# 2230506226.net
KiCad netlist of a schematic drawn in EasyEDA Pro
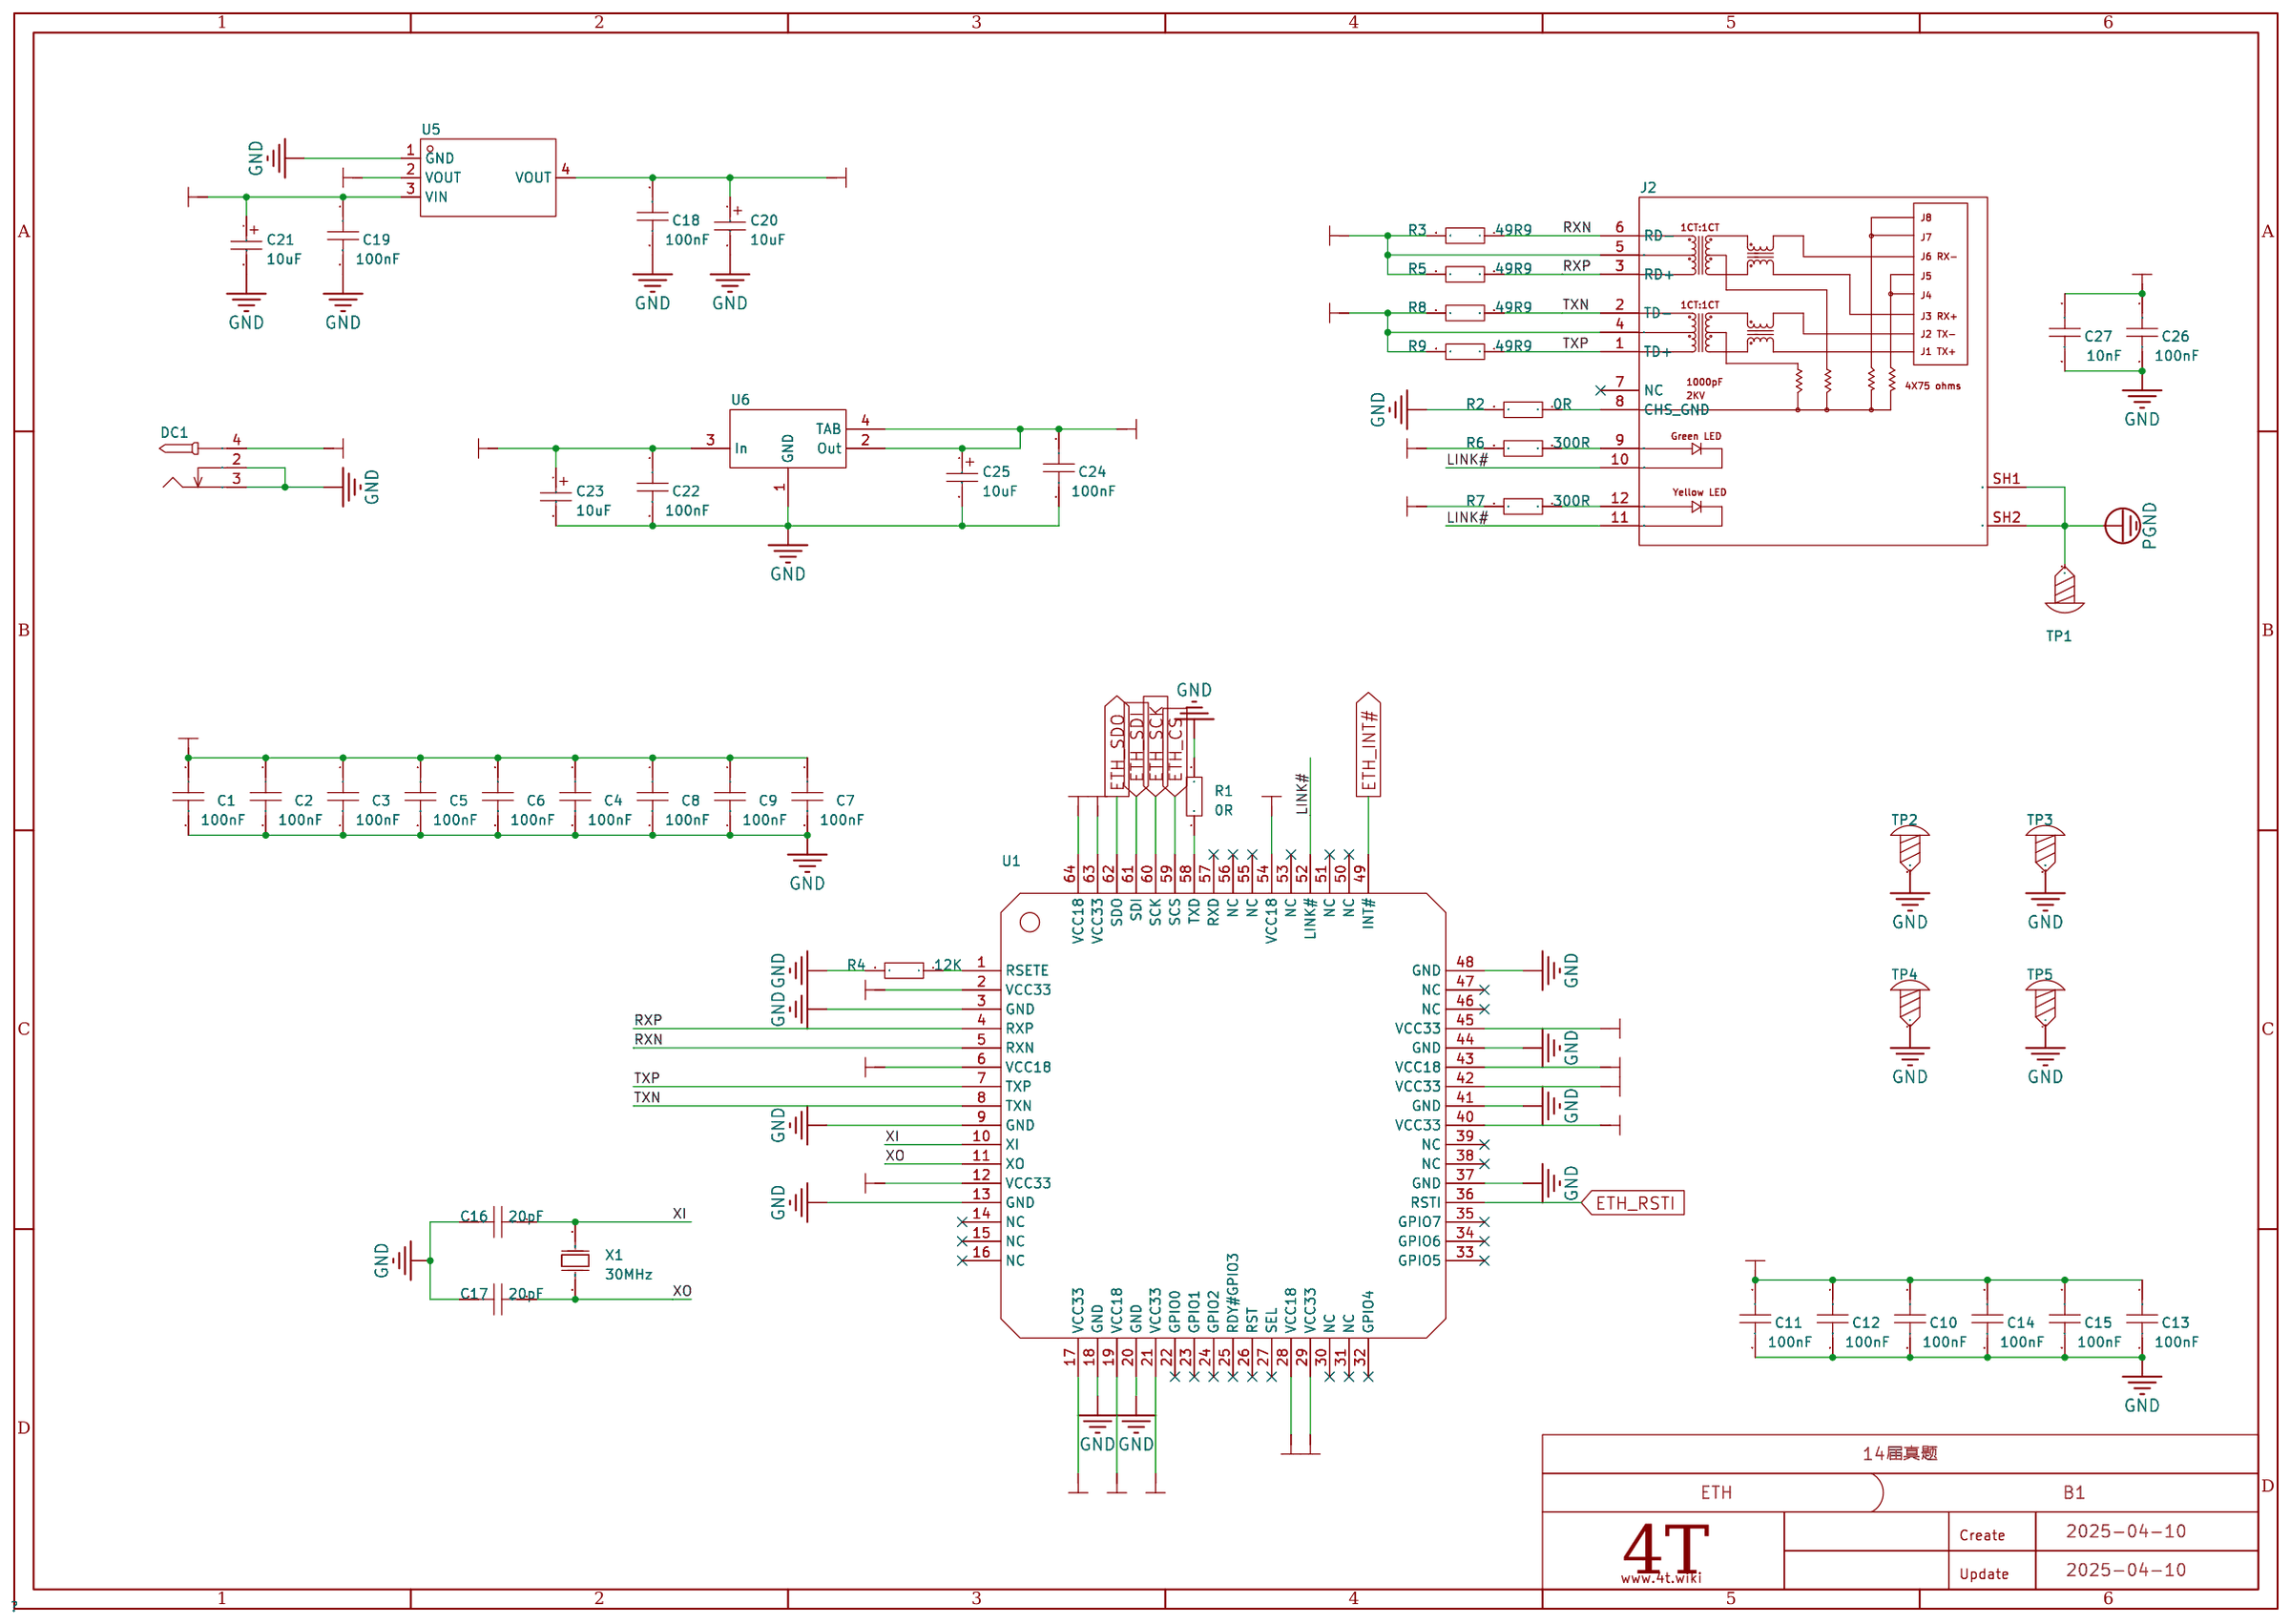
[diagram p0: ETH]
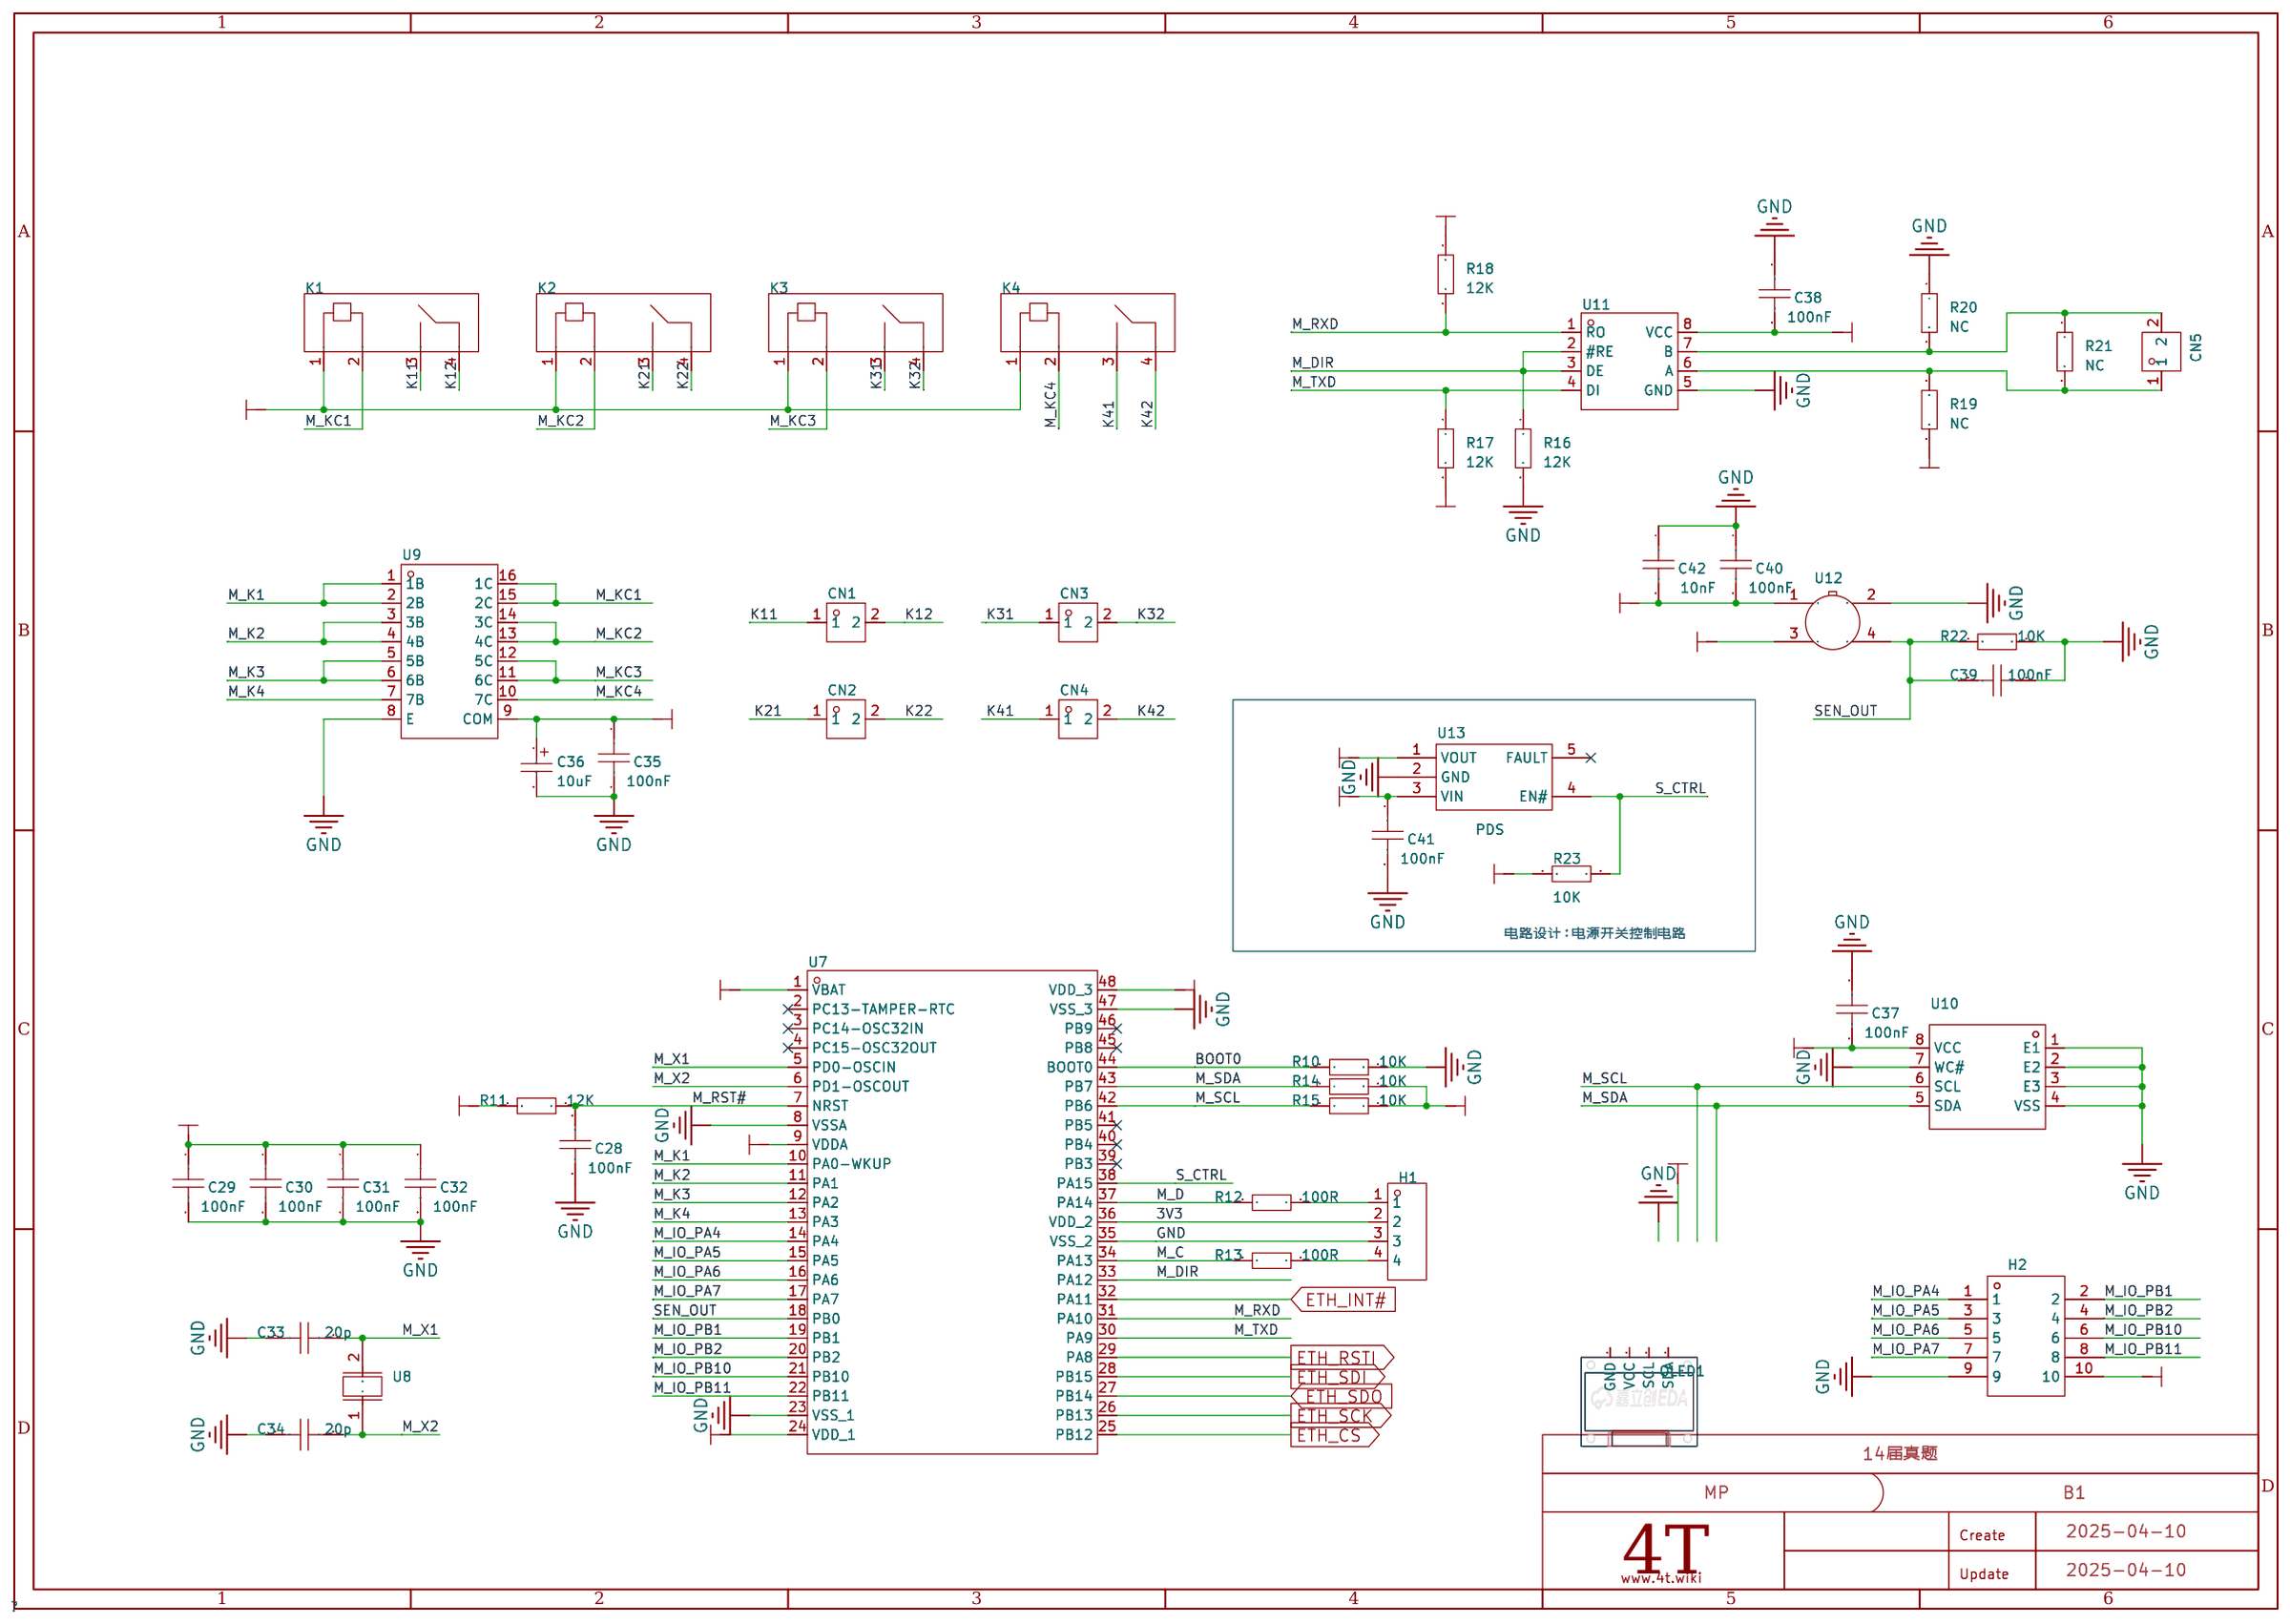
[diagram p1: MP]

(export (version "E")
  (design (tool "Eeschema 10.0.6"))
  (components
    (comp (ref "C1")
      (value "100nF")
      (footprint "easyedapro:C0805")
      (libsource (lib "easyedapro") (part "CapAcitance"))
    )
    (comp (ref "C2")
      (value "100nF")
      (footprint "easyedapro:C0805")
      (libsource (lib "easyedapro") (part "CapAcitance"))
    )
    (comp (ref "C3")
      (value "100nF")
      (footprint "easyedapro:C0805")
      (libsource (lib "easyedapro") (part "CapAcitance"))
    )
    (comp (ref "C4")
      (value "100nF")
      (footprint "easyedapro:C0805")
      (libsource (lib "easyedapro") (part "CapAcitance"))
    )
    (comp (ref "C5")
      (value "100nF")
      (footprint "easyedapro:C0805")
      (libsource (lib "easyedapro") (part "CapAcitance"))
    )
    (comp (ref "C6")
      (value "100nF")
      (footprint "easyedapro:C0805")
      (libsource (lib "easyedapro") (part "CapAcitance"))
    )
    (comp (ref "C7")
      (value "100nF")
      (footprint "easyedapro:C0805")
      (libsource (lib "easyedapro") (part "CapAcitance"))
    )
    (comp (ref "C8")
      (value "100nF")
      (footprint "easyedapro:C0805")
      (libsource (lib "easyedapro") (part "CapAcitance"))
    )
    (comp (ref "C9")
      (value "100nF")
      (footprint "easyedapro:C0805")
      (libsource (lib "easyedapro") (part "CapAcitance"))
    )
    (comp (ref "C10")
      (value "100nF")
      (footprint "easyedapro:C0805")
      (libsource (lib "easyedapro") (part "CapAcitance"))
    )
    (comp (ref "C11")
      (value "100nF")
      (footprint "easyedapro:C0805")
      (libsource (lib "easyedapro") (part "CapAcitance"))
    )
    (comp (ref "C12")
      (value "100nF")
      (footprint "easyedapro:C0805")
      (libsource (lib "easyedapro") (part "CapAcitance"))
    )
    (comp (ref "C13")
      (value "100nF")
      (footprint "easyedapro:C0805")
      (libsource (lib "easyedapro") (part "CapAcitance"))
    )
    (comp (ref "C14")
      (value "100nF")
      (footprint "easyedapro:C0805")
      (libsource (lib "easyedapro") (part "CapAcitance"))
    )
    (comp (ref "C15")
      (value "100nF")
      (footprint "easyedapro:C0805")
      (libsource (lib "easyedapro") (part "CapAcitance"))
    )
    (comp (ref "C16")
      (value "20pF")
      (footprint "easyedapro:C0805")
      (libsource (lib "easyedapro") (part "CapAcitance"))
    )
    (comp (ref "C17")
      (value "20pF")
      (footprint "easyedapro:C0805")
      (libsource (lib "easyedapro") (part "CapAcitance"))
    )
    (comp (ref "C18")
      (value "100nF")
      (footprint "easyedapro:C0805")
      (libsource (lib "easyedapro") (part "CapAcitance"))
    )
    (comp (ref "C19")
      (value "100nF")
      (footprint "easyedapro:C0805")
      (libsource (lib "easyedapro") (part "CapAcitance"))
    )
    (comp (ref "C20")
      (value "10uF")
      (footprint "easyedapro:C_Ele_SMD_3x5.4mm")
      (libsource (lib "easyedapro") (part "CAP"))
    )
    (comp (ref "C21")
      (value "10uF")
      (footprint "easyedapro:C_Ele_SMD_3x5.4mm")
      (libsource (lib "easyedapro") (part "CAP"))
    )
    (comp (ref "C22")
      (value "100nF")
      (footprint "easyedapro:C0805")
      (libsource (lib "easyedapro") (part "CapAcitance"))
    )
    (comp (ref "C23")
      (value "10uF")
      (footprint "easyedapro:C_Ele_SMD_3x5.4mm")
      (libsource (lib "easyedapro") (part "CAP"))
    )
    (comp (ref "C24")
      (value "100nF")
      (footprint "easyedapro:C0805")
      (libsource (lib "easyedapro") (part "CapAcitance"))
    )
    (comp (ref "C25")
      (value "10uF")
      (footprint "easyedapro:C_Ele_SMD_3x5.4mm")
      (libsource (lib "easyedapro") (part "CAP"))
    )
    (comp (ref "C26")
      (value "100nF")
      (footprint "easyedapro:C0805")
      (libsource (lib "easyedapro") (part "CapAcitance"))
    )
    (comp (ref "C27")
      (value "10nF")
      (footprint "easyedapro:C0805")
      (libsource (lib "easyedapro") (part "CapAcitance"))
    )
    (comp (ref "DC1")
      (value "~")
      (footprint "easyedapro:DC-2.0")
      (libsource (lib "easyedapro") (part "DC电源接口"))
    )
    (comp (ref "J2")
      (value "HY911105AE")
      (footprint "easyedapro:RJ45-TH_HR911105A")
      (description "连接器类型:RJ插座;USOC代码:RJ45;端口数量:1;等级:-;屏蔽:-;LED:-;")
      (fields (field (name "Manufacturer") "HANRUN(汉仁)"))
      (libsource (lib "easyedapro") (part "HY911105AE"))
    )
    (comp (ref "R1") (value "0R") (footprint "easyedapro:R0805") (libsource (lib "easyedapro") (part "电阻")))
    (comp (ref "R2") (value "0R") (footprint "easyedapro:R0805") (libsource (lib "easyedapro") (part "电阻")))
    (comp (ref "R3") (value "49R9") (footprint "easyedapro:R0805") (libsource (lib "easyedapro") (part "电阻")))
    (comp (ref "R4") (value "12K") (footprint "easyedapro:R0805") (libsource (lib "easyedapro") (part "电阻")))
    (comp (ref "R5") (value "49R9") (footprint "easyedapro:R0805") (libsource (lib "easyedapro") (part "电阻")))
    (comp (ref "R6") (value "300R") (footprint "easyedapro:R0805") (libsource (lib "easyedapro") (part "电阻")))
    (comp (ref "R7") (value "300R") (footprint "easyedapro:R0805") (libsource (lib "easyedapro") (part "电阻")))
    (comp (ref "R8") (value "49R9") (footprint "easyedapro:R0805") (libsource (lib "easyedapro") (part "电阻")))
    (comp (ref "R9") (value "49R9") (footprint "easyedapro:R0805") (libsource (lib "easyedapro") (part "电阻")))
    (comp (ref "TP1") (value "~") (footprint "easyedapro:M2螺丝") (libsource (lib "easyedapro") (part "螺丝孔")))
    (comp (ref "TP2") (value "~") (footprint "easyedapro:M2螺丝") (libsource (lib "easyedapro") (part "螺丝孔")))
    (comp (ref "TP3") (value "~") (footprint "easyedapro:M2螺丝") (libsource (lib "easyedapro") (part "螺丝孔")))
    (comp (ref "TP4") (value "~") (footprint "easyedapro:M2螺丝") (libsource (lib "easyedapro") (part "螺丝孔")))
    (comp (ref "TP5") (value "~") (footprint "easyedapro:M2螺丝") (libsource (lib "easyedapro") (part "螺丝孔")))
    (comp (ref "U1")
      (value "CH395Q")
      (footprint "easyedapro:LQFP-64_L10.0-W10.0-P0.50-LS12.0-BL")
      (description "应用功能:以太网控制器;通道数:-;接口类型:Parallel, SPI, UART;电源电压:1.65V~3.6V;电源电流:90mA;")
      (fields (field (name "Manufacturer") "WCH(南京沁恒)"))
      (libsource (lib "easyedapro") (part "CH395Q"))
    )
    (comp (ref "U5")
      (value "AMS1117-3.3")
      (footprint "easyedapro:SOT-223-3_L6.5-W3.4-P2.30-LS7.0-BR")
      (fields (field (name "Manufacturer") "AMS"))
      (libsource (lib "easyedapro") (part "AMS1117-3.3"))
    )
    (comp (ref "U6")
      (value "AMS1117-1.8")
      (footprint "easyedapro:SOT-223-4_L6.5-W3.5-P2.30-LS7.0-BR")
      (description "输出类型:固定;输出极性:正;输出通道数:1;最大输入电压:15V;输出电压:1.8V~1.8V;压差:1.3V@(1A);输出电流:1A;电源纹波抑制比(PSRR):75dB@(120Hz);")
      (fields (field (name "Manufacturer") "AMS"))
      (libsource (lib "easyedapro") (part "AMS1117-1.8"))
    )
    (comp (ref "X1")
      (value "30MHz")
      (footprint "easyedapro:OSC-SMD_L5.0-W3.2")
      (description "晶振类型:贴片无源晶振;频率:30MHz;频率公差:±10ppm;频率稳定度:±50ppm;负载电容:20pF;工作温度:-40°C~+85°C;")
      (fields (field (name "Manufacturer Part") "X503230MSB2GI") (field (name "Manufacturer") "YXC(扬兴晶振)"))
      (libsource (lib "easyedapro") (part "X503230MSB2GI"))
    )
    (comp (ref "C28")
      (value "100nF")
      (footprint "easyedapro:C0805")
      (libsource (lib "easyedapro") (part "CapAcitance"))
    )
    (comp (ref "C29")
      (value "100nF")
      (footprint "easyedapro:C0805")
      (libsource (lib "easyedapro") (part "CapAcitance"))
    )
    (comp (ref "C30")
      (value "100nF")
      (footprint "easyedapro:C0805")
      (libsource (lib "easyedapro") (part "CapAcitance"))
    )
    (comp (ref "C31")
      (value "100nF")
      (footprint "easyedapro:C0805")
      (libsource (lib "easyedapro") (part "CapAcitance"))
    )
    (comp (ref "C32")
      (value "100nF")
      (footprint "easyedapro:C0805")
      (libsource (lib "easyedapro") (part "CapAcitance"))
    )
    (comp (ref "C33")
      (value "20p")
      (footprint "easyedapro:C0805")
      (libsource (lib "easyedapro") (part "CapAcitance"))
    )
    (comp (ref "C34")
      (value "20p")
      (footprint "easyedapro:C0805")
      (libsource (lib "easyedapro") (part "CapAcitance"))
    )
    (comp (ref "C35")
      (value "100nF")
      (footprint "easyedapro:C0805")
      (libsource (lib "easyedapro") (part "CapAcitance"))
    )
    (comp (ref "C36")
      (value "10uF")
      (footprint "easyedapro:C_Ele_SMD_3x5.4mm")
      (libsource (lib "easyedapro") (part "CAP"))
    )
    (comp (ref "C37")
      (value "100nF")
      (footprint "easyedapro:C0805")
      (libsource (lib "easyedapro") (part "CapAcitance"))
    )
    (comp (ref "C38")
      (value "100nF")
      (footprint "easyedapro:C0805")
      (libsource (lib "easyedapro") (part "CapAcitance"))
    )
    (comp (ref "C39")
      (value "100nF")
      (footprint "easyedapro:C0805")
      (libsource (lib "easyedapro") (part "CapAcitance"))
    )
    (comp (ref "C40")
      (value "100nF")
      (footprint "easyedapro:C0805")
      (libsource (lib "easyedapro") (part "CapAcitance"))
    )
    (comp (ref "C41")
      (value "100nF")
      (footprint "easyedapro:C0805")
      (libsource (lib "easyedapro") (part "CapAcitance"))
    )
    (comp (ref "C42")
      (value "10nF")
      (footprint "easyedapro:C0805")
      (libsource (lib "easyedapro") (part "CapAcitance"))
    )
    (comp (ref "CN1")
      (value "KF128L-5.08-2P 蓝色")
      (footprint "easyedapro:TH_KF128L-5.08-2P")
      (libsource (lib "easyedapro") (part "KF128L-5.08-2P 蓝色"))
    )
    (comp (ref "CN2")
      (value "KF128L-5.08-2P 蓝色")
      (footprint "easyedapro:TH_KF128L-5.08-2P")
      (libsource (lib "easyedapro") (part "KF128L-5.08-2P 蓝色"))
    )
    (comp (ref "CN3")
      (value "KF128L-5.08-2P 蓝色")
      (footprint "easyedapro:TH_KF128L-5.08-2P")
      (libsource (lib "easyedapro") (part "KF128L-5.08-2P 蓝色"))
    )
    (comp (ref "CN4")
      (value "KF128L-5.08-2P 蓝色")
      (footprint "easyedapro:TH_KF128L-5.08-2P")
      (libsource (lib "easyedapro") (part "KF128L-5.08-2P 蓝色"))
    )
    (comp (ref "CN5")
      (value "KF128L-5.08-2P 蓝色")
      (footprint "easyedapro:TH_KF128L-5.08-2P")
      (libsource (lib "easyedapro") (part "KF128L-5.08-2P 蓝色"))
    )
    (comp (ref "H1")
      (value "~")
      (footprint "easyedapro:HDR-TH_4P-P2.54-V-F")
      (libsource (lib "easyedapro") (part "2.54-1*4P母"))
    )
    (comp (ref "H2")
      (value "~")
      (footprint "easyedapro:HDR-TH_10P-P2.54-V-M-R2-C5-S2.54")
      (libsource (lib "easyedapro") (part "HDR-M-2.54_2x5"))
    )
    (comp (ref "K1")
      (value "HF49FD/012-1H12")
      (footprint "easyedapro:RELAY-TH_HF49FD-XXX-1H12-XXX")
      (description "线圈电压:12V;线圈类型:非极化-单线圈;触点形式:一组常开:1A(单刀单掷-常开);最大切换电流:5A;触点材料:AgNi;")
      (fields (field (name "Manufacturer") "HF(宏发)"))
      (libsource (lib "easyedapro") (part "HF49FD/012-1H12"))
    )
    (comp (ref "K2")
      (value "HF49FD/012-1H12")
      (footprint "easyedapro:RELAY-TH_HF49FD-XXX-1H12-XXX")
      (description "线圈电压:12V;线圈类型:非极化-单线圈;触点形式:一组常开:1A(单刀单掷-常开);最大切换电流:5A;触点材料:AgNi;")
      (fields (field (name "Manufacturer") "HF(宏发)"))
      (libsource (lib "easyedapro") (part "HF49FD/012-1H12"))
    )
    (comp (ref "K3")
      (value "HF49FD/012-1H12")
      (footprint "easyedapro:RELAY-TH_HF49FD-XXX-1H12-XXX")
      (description "线圈电压:12V;线圈类型:非极化-单线圈;触点形式:一组常开:1A(单刀单掷-常开);最大切换电流:5A;触点材料:AgNi;")
      (fields (field (name "Manufacturer") "HF(宏发)"))
      (libsource (lib "easyedapro") (part "HF49FD/012-1H12"))
    )
    (comp (ref "K4")
      (value "HF49FD/012-1H12")
      (footprint "easyedapro:RELAY-TH_HF49FD-XXX-1H12-XXX")
      (description "线圈电压:12V;线圈类型:非极化-单线圈;触点形式:一组常开:1A(单刀单掷-常开);最大切换电流:5A;触点材料:AgNi;")
      (fields (field (name "Manufacturer") "HF(宏发)"))
      (libsource (lib "easyedapro") (part "HF49FD/012-1H12"))
    )
    (comp (ref "OLED1")
      (value "~")
      (footprint "easyedapro:0.96OLED_4P")
      (libsource (lib "easyedapro") (part "0.96OLED模块_4P"))
    )
    (comp (ref "R10") (value "10K") (footprint "easyedapro:R0805") (libsource (lib "easyedapro") (part "电阻")))
    (comp (ref "R11") (value "12K") (footprint "easyedapro:R0805") (libsource (lib "easyedapro") (part "电阻")))
    (comp (ref "R12")
      (value "100R")
      (footprint "easyedapro:R0805")
      (libsource (lib "easyedapro") (part "电阻"))
    )
    (comp (ref "R13")
      (value "100R")
      (footprint "easyedapro:R0805")
      (libsource (lib "easyedapro") (part "电阻"))
    )
    (comp (ref "R14") (value "10K") (footprint "easyedapro:R0805") (libsource (lib "easyedapro") (part "电阻")))
    (comp (ref "R15") (value "10K") (footprint "easyedapro:R0805") (libsource (lib "easyedapro") (part "电阻")))
    (comp (ref "R16") (value "12K") (footprint "easyedapro:R0805") (libsource (lib "easyedapro") (part "电阻")))
    (comp (ref "R17") (value "12K") (footprint "easyedapro:R0805") (libsource (lib "easyedapro") (part "电阻")))
    (comp (ref "R18") (value "12K") (footprint "easyedapro:R0805") (libsource (lib "easyedapro") (part "电阻")))
    (comp (ref "R19") (value "NC") (footprint "easyedapro:R0805") (libsource (lib "easyedapro") (part "电阻")))
    (comp (ref "R20") (value "NC") (footprint "easyedapro:R0805") (libsource (lib "easyedapro") (part "电阻")))
    (comp (ref "R21") (value "NC") (footprint "easyedapro:R0805") (libsource (lib "easyedapro") (part "电阻")))
    (comp (ref "R22") (value "10K") (footprint "easyedapro:R0805") (libsource (lib "easyedapro") (part "电阻")))
    (comp (ref "R23") (value "10K") (footprint "easyedapro:R0805") (libsource (lib "easyedapro") (part "电阻")))
    (comp (ref "U7")
      (value "GD32F303CBT6")
      (footprint "easyedapro:LQFP-48_L7.0-W7.0-P0.50-LS9.0-BL")
      (fields (field (name "Manufacturer") "GigaDevice(兆易创新)"))
      (libsource (lib "easyedapro") (part "GD32F303CBT6"))
    )
    (comp (ref "U8")
      (value "8M-5032-2P")
      (footprint "easyedapro:CRYSTAL-SMD_L5.0-W3.2")
      (libsource (lib "easyedapro") (part "8M-5032-2P"))
    )
    (comp (ref "U9")
      (value "ULN2003")
      (footprint "easyedapro:SOIC-16_L9.9-W3.9-P1.27-LS6.0-BL")
      (fields (field (name "Manufacturer") "IDCHIP(英锐芯)"))
      (libsource (lib "easyedapro") (part "ULN2003_C688859"))
    )
    (comp (ref "U10")
      (value "M24C02-WMN6TP")
      (footprint "easyedapro:SOIC-8_L4.9-W3.9-P1.27-LS6.0-BL")
      (description "2-Kbit(256 x 8bit)，I2C接口，工作电压：2.5V to 5.5V")
      (fields (field (name "Manufacturer") "ST(意法半导体)"))
      (libsource (lib "easyedapro") (part "M24C02-WMN6TP"))
    )
    (comp (ref "U11")
      (value "MAX3485ESA")
      (footprint "easyedapro:SOP-8_L5.0-W4.0-P1.27-LS6.0-BL")
      (fields (field (name "Manufacturer") "UMW(广东友台半导体)"))
      (libsource (lib "easyedapro") (part "MAX3485ESA"))
    )
    (comp (ref "U12")
      (value "MP-2")
      (footprint "easyedapro:SENSOR-TH_MP-5")
      (fields (field (name "Manufacturer") "Winsen(炜盛)"))
      (libsource (lib "easyedapro") (part "MP-2"))
    )
    (comp (ref "U13") (value "PDS") (libsource (lib "easyedapro") (part "PDS")))
  )
  (nets
    (net (code "1") (name "1V8") (class "Default")
      (node (ref "C10") (pin "1") (pinfunction "1_1") (pintype "input"))
      (node (ref "C11") (pin "1") (pinfunction "1_1") (pintype "input"))
      (node (ref "C12") (pin "1") (pinfunction "1_1") (pintype "input"))
      (node (ref "C13") (pin "1") (pinfunction "1_1") (pintype "input"))
      (node (ref "C14") (pin "1") (pinfunction "1_1") (pintype "input"))
      (node (ref "C15") (pin "1") (pinfunction "1_1") (pintype "input"))
      (node (ref "C24") (pin "1") (pinfunction "1_1") (pintype "input"))
      (node (ref "C25") (pin "1") (pinfunction "1_1") (pintype "input"))
      (node (ref "U1") (pin "19") (pinfunction "VCC18_19") (pintype "input"))
      (node (ref "U1") (pin "28") (pinfunction "VCC18_28") (pintype "input"))
      (node (ref "U1") (pin "43") (pinfunction "VCC18_43") (pintype "input"))
      (node (ref "U1") (pin "54") (pinfunction "VCC18_54") (pintype "input"))
      (node (ref "U1") (pin "6") (pinfunction "VCC18_6") (pintype "input"))
      (node (ref "U1") (pin "63") (pinfunction "VCC33_63") (pintype "input"))
      (node (ref "U6") (pin "2") (pinfunction "Out_2") (pintype "input"))
      (node (ref "U6") (pin "4") (pinfunction "TAB_4") (pintype "input"))
    )
    (net (code "2") (name "3V3") (class "Default")
      (node (ref "C1") (pin "1") (pinfunction "1_1") (pintype "input"))
      (node (ref "C18") (pin "1") (pinfunction "1_1") (pintype "input"))
      (node (ref "C2") (pin "1") (pinfunction "1_1") (pintype "input"))
      (node (ref "C20") (pin "1") (pinfunction "1_1") (pintype "input"))
      (node (ref "C22") (pin "1") (pinfunction "1_1") (pintype "input"))
      (node (ref "C23") (pin "1") (pinfunction "1_1") (pintype "input"))
      (node (ref "C26") (pin "1") (pinfunction "1_1") (pintype "input"))
      (node (ref "C27") (pin "1") (pinfunction "1_1") (pintype "input"))
      (node (ref "C29") (pin "1") (pinfunction "1_1") (pintype "input"))
      (node (ref "C3") (pin "1") (pinfunction "1_1") (pintype "input"))
      (node (ref "C30") (pin "1") (pinfunction "1_1") (pintype "input"))
      (node (ref "C31") (pin "1") (pinfunction "1_1") (pintype "input"))
      (node (ref "C32") (pin "1") (pinfunction "1_1") (pintype "input"))
      (node (ref "C37") (pin "2") (pinfunction "2_2") (pintype "input"))
      (node (ref "C38") (pin "2") (pinfunction "2_2") (pintype "input"))
      (node (ref "C4") (pin "1") (pinfunction "1_1") (pintype "input"))
      (node (ref "C5") (pin "1") (pinfunction "1_1") (pintype "input"))
      (node (ref "C6") (pin "1") (pinfunction "1_1") (pintype "input"))
      (node (ref "C7") (pin "1") (pinfunction "1_1") (pintype "input"))
      (node (ref "C8") (pin "1") (pinfunction "1_1") (pintype "input"))
      (node (ref "C9") (pin "1") (pinfunction "1_1") (pintype "input"))
      (node (ref "H1") (pin "2") (pinfunction "2_2") (pintype "input"))
      (node (ref "H2") (pin "10") (pinfunction "10_10") (pintype "input"))
      (node (ref "J2") (pin "4") (pinfunction "4_4") (pintype "input"))
      (node (ref "J2") (pin "5") (pinfunction "5_5") (pintype "input"))
      (node (ref "R11") (pin "2") (pinfunction "2_2") (pintype "input"))
      (node (ref "R14") (pin "2") (pinfunction "2_2") (pintype "input"))
      (node (ref "R15") (pin "1") (pinfunction "1_1") (pintype "input"))
      (node (ref "R17") (pin "2") (pinfunction "2_2") (pintype "input"))
      (node (ref "R18") (pin "1") (pinfunction "1_1") (pintype "input"))
      (node (ref "R19") (pin "2") (pinfunction "2_2") (pintype "input"))
      (node (ref "R23") (pin "1") (pinfunction "1_1") (pintype "input"))
      (node (ref "R3") (pin "2") (pinfunction "2_2") (pintype "input"))
      (node (ref "R5") (pin "2") (pinfunction "2_2") (pintype "input"))
      (node (ref "R6") (pin "2") (pinfunction "2_2") (pintype "input"))
      (node (ref "R7") (pin "2") (pinfunction "2_2") (pintype "input"))
      (node (ref "R8") (pin "2") (pinfunction "2_2") (pintype "input"))
      (node (ref "R9") (pin "2") (pinfunction "2_2") (pintype "input"))
      (node (ref "U1") (pin "12") (pinfunction "VCC33_12") (pintype "input"))
      (node (ref "U1") (pin "17") (pinfunction "VCC33_17") (pintype "input"))
      (node (ref "U1") (pin "2") (pinfunction "VCC33_2") (pintype "input"))
      (node (ref "U1") (pin "21") (pinfunction "VCC33_21") (pintype "input"))
      (node (ref "U1") (pin "29") (pinfunction "VCC33_29") (pintype "input"))
      (node (ref "U1") (pin "40") (pinfunction "VCC33_40") (pintype "input"))
      (node (ref "U1") (pin "42") (pinfunction "VCC33_42") (pintype "input"))
      (node (ref "U1") (pin "45") (pinfunction "VCC33_45") (pintype "input"))
      (node (ref "U1") (pin "64") (pinfunction "VCC18_64") (pintype "input"))
      (node (ref "U10") (pin "8") (pinfunction "VCC_8") (pintype "input"))
      (node (ref "U11") (pin "8") (pinfunction "VCC_8") (pintype "input"))
      (node (ref "U12") (pin "3") (pinfunction "3_3") (pintype "input"))
      (node (ref "U5") (pin "2") (pinfunction "VOUT_2") (pintype "input"))
      (node (ref "U5") (pin "4") (pinfunction "VOUT_4") (pintype "input"))
      (node (ref "U6") (pin "3") (pinfunction "In_3") (pintype "input"))
      (node (ref "U7") (pin "1") (pinfunction "VBAT_1") (pintype "input"))
      (node (ref "U7") (pin "24") (pinfunction "VDD_1_24") (pintype "input"))
      (node (ref "U7") (pin "36") (pinfunction "VDD_2_36") (pintype "input"))
      (node (ref "U7") (pin "48") (pinfunction "VDD_3_48") (pintype "input"))
      (node (ref "U7") (pin "9") (pinfunction "VDDA_9") (pintype "input"))
    )
    (net (code "3") (name "BOOT0") (class "Default")
      (node (ref "R10") (pin "2") (pinfunction "2_2") (pintype "input"))
      (node (ref "U7") (pin "44") (pinfunction "BOOT0_44") (pintype "input"))
    )
    (net (code "4") (name "DC") (class "Default")
      (node (ref "C19") (pin "1") (pinfunction "1_1") (pintype "input"))
      (node (ref "C21") (pin "1") (pinfunction "1_1") (pintype "input"))
      (node (ref "C35") (pin "1") (pinfunction "1_1") (pintype "input"))
      (node (ref "C36") (pin "1") (pinfunction "1_1") (pintype "input"))
      (node (ref "C41") (pin "1") (pinfunction "1_1") (pintype "input"))
      (node (ref "DC1") (pin "4") (pinfunction "4_4") (pintype "input"))
      (node (ref "K1") (pin "1") (pinfunction "1_1") (pintype "input"))
      (node (ref "K2") (pin "1") (pinfunction "1_1") (pintype "input"))
      (node (ref "K3") (pin "1") (pinfunction "1_1") (pintype "input"))
      (node (ref "K4") (pin "1") (pinfunction "1_1") (pintype "input"))
      (node (ref "U13") (pin "3") (pinfunction "VIN_3") (pintype "input"))
      (node (ref "U5") (pin "3") (pinfunction "VIN_3") (pintype "input"))
      (node (ref "U9") (pin "9") (pinfunction "COM_9") (pintype "input"))
    )
    (net (code "5") (name "ETH_CS") (class "Default")
      (node (ref "U1") (pin "59") (pinfunction "SCS_59") (pintype "input"))
      (node (ref "U7") (pin "25") (pinfunction "PB12_25") (pintype "input"))
    )
    (net (code "6") (name "ETH_INT#") (class "Default")
      (node (ref "U1") (pin "49") (pinfunction "INT#_49") (pintype "input"))
      (node (ref "U7") (pin "32") (pinfunction "PA11_32") (pintype "input"))
    )
    (net (code "7") (name "ETH_RSTI") (class "Default")
      (node (ref "U1") (pin "36") (pinfunction "RSTI_36") (pintype "input"))
      (node (ref "U7") (pin "29") (pinfunction "PA8_29") (pintype "input"))
    )
    (net (code "8") (name "ETH_SCK") (class "Default")
      (node (ref "U1") (pin "60") (pinfunction "SCK_60") (pintype "input"))
      (node (ref "U7") (pin "26") (pinfunction "PB13_26") (pintype "input"))
    )
    (net (code "9") (name "ETH_SDI") (class "Default")
      (node (ref "U1") (pin "61") (pinfunction "SDI_61") (pintype "input"))
      (node (ref "U7") (pin "28") (pinfunction "PB15_28") (pintype "input"))
    )
    (net (code "10") (name "ETH_SDO") (class "Default")
      (node (ref "U1") (pin "62") (pinfunction "SDO_62") (pintype "input"))
      (node (ref "U7") (pin "27") (pinfunction "PB14_27") (pintype "input"))
    )
    (net (code "11") (name "GND") (class "Default")
      (node (ref "C1") (pin "2") (pinfunction "2_2") (pintype "input"))
      (node (ref "C10") (pin "2") (pinfunction "2_2") (pintype "input"))
      (node (ref "C11") (pin "2") (pinfunction "2_2") (pintype "input"))
      (node (ref "C12") (pin "2") (pinfunction "2_2") (pintype "input"))
      (node (ref "C13") (pin "2") (pinfunction "2_2") (pintype "input"))
      (node (ref "C14") (pin "2") (pinfunction "2_2") (pintype "input"))
      (node (ref "C15") (pin "2") (pinfunction "2_2") (pintype "input"))
      (node (ref "C16") (pin "1") (pinfunction "1_1") (pintype "input"))
      (node (ref "C17") (pin "1") (pinfunction "1_1") (pintype "input"))
      (node (ref "C18") (pin "2") (pinfunction "2_2") (pintype "input"))
      (node (ref "C19") (pin "2") (pinfunction "2_2") (pintype "input"))
      (node (ref "C2") (pin "2") (pinfunction "2_2") (pintype "input"))
      (node (ref "C20") (pin "2") (pinfunction "2_2") (pintype "input"))
      (node (ref "C21") (pin "2") (pinfunction "2_2") (pintype "input"))
      (node (ref "C22") (pin "2") (pinfunction "2_2") (pintype "input"))
      (node (ref "C23") (pin "2") (pinfunction "2_2") (pintype "input"))
      (node (ref "C24") (pin "2") (pinfunction "2_2") (pintype "input"))
      (node (ref "C25") (pin "2") (pinfunction "2_2") (pintype "input"))
      (node (ref "C26") (pin "2") (pinfunction "2_2") (pintype "input"))
      (node (ref "C27") (pin "2") (pinfunction "2_2") (pintype "input"))
      (node (ref "C28") (pin "2") (pinfunction "2_2") (pintype "input"))
      (node (ref "C29") (pin "2") (pinfunction "2_2") (pintype "input"))
      (node (ref "C3") (pin "2") (pinfunction "2_2") (pintype "input"))
      (node (ref "C30") (pin "2") (pinfunction "2_2") (pintype "input"))
      (node (ref "C31") (pin "2") (pinfunction "2_2") (pintype "input"))
      (node (ref "C32") (pin "2") (pinfunction "2_2") (pintype "input"))
      (node (ref "C33") (pin "1") (pinfunction "1_1") (pintype "input"))
      (node (ref "C34") (pin "1") (pinfunction "1_1") (pintype "input"))
      (node (ref "C35") (pin "2") (pinfunction "2_2") (pintype "input"))
      (node (ref "C36") (pin "2") (pinfunction "2_2") (pintype "input"))
      (node (ref "C37") (pin "1") (pinfunction "1_1") (pintype "input"))
      (node (ref "C38") (pin "1") (pinfunction "1_1") (pintype "input"))
      (node (ref "C39") (pin "2") (pinfunction "2_2") (pintype "input"))
      (node (ref "C4") (pin "2") (pinfunction "2_2") (pintype "input"))
      (node (ref "C40") (pin "1") (pinfunction "1_1") (pintype "input"))
      (node (ref "C41") (pin "2") (pinfunction "2_2") (pintype "input"))
      (node (ref "C42") (pin "1") (pinfunction "1_1") (pintype "input"))
      (node (ref "C5") (pin "2") (pinfunction "2_2") (pintype "input"))
      (node (ref "C6") (pin "2") (pinfunction "2_2") (pintype "input"))
      (node (ref "C7") (pin "2") (pinfunction "2_2") (pintype "input"))
      (node (ref "C8") (pin "2") (pinfunction "2_2") (pintype "input"))
      (node (ref "C9") (pin "2") (pinfunction "2_2") (pintype "input"))
      (node (ref "DC1") (pin "2") (pinfunction "2_2") (pintype "input"))
      (node (ref "DC1") (pin "3") (pinfunction "3_3") (pintype "input"))
      (node (ref "H1") (pin "3") (pinfunction "3_3") (pintype "input"))
      (node (ref "H2") (pin "9") (pinfunction "9_9") (pintype "input"))
      (node (ref "R1") (pin "2") (pinfunction "2_2") (pintype "input"))
      (node (ref "R10") (pin "1") (pinfunction "1_1") (pintype "input"))
      (node (ref "R16") (pin "2") (pinfunction "2_2") (pintype "input"))
      (node (ref "R2") (pin "2") (pinfunction "2_2") (pintype "input"))
      (node (ref "R20") (pin "1") (pinfunction "1_1") (pintype "input"))
      (node (ref "R22") (pin "2") (pinfunction "2_2") (pintype "input"))
      (node (ref "R4") (pin "2") (pinfunction "2_2") (pintype "input"))
      (node (ref "TP2") (pin "1") (pinfunction "1_1") (pintype "input"))
      (node (ref "TP3") (pin "1") (pinfunction "1_1") (pintype "input"))
      (node (ref "TP4") (pin "1") (pinfunction "1_1") (pintype "input"))
      (node (ref "TP5") (pin "1") (pinfunction "1_1") (pintype "input"))
      (node (ref "U1") (pin "13") (pinfunction "GND_13") (pintype "input"))
      (node (ref "U1") (pin "18") (pinfunction "GND_18") (pintype "input"))
      (node (ref "U1") (pin "20") (pinfunction "GND_20") (pintype "input"))
      (node (ref "U1") (pin "3") (pinfunction "GND_3") (pintype "input"))
      (node (ref "U1") (pin "37") (pinfunction "GND_37") (pintype "input"))
      (node (ref "U1") (pin "41") (pinfunction "GND_41") (pintype "input"))
      (node (ref "U1") (pin "44") (pinfunction "GND_44") (pintype "input"))
      (node (ref "U1") (pin "48") (pinfunction "GND_48") (pintype "input"))
      (node (ref "U1") (pin "9") (pinfunction "GND_9") (pintype "input"))
      (node (ref "U10") (pin "1") (pinfunction "E1_1") (pintype "input"))
      (node (ref "U10") (pin "2") (pinfunction "E2_2") (pintype "input"))
      (node (ref "U10") (pin "3") (pinfunction "E3_3") (pintype "input"))
      (node (ref "U10") (pin "4") (pinfunction "VSS_4") (pintype "input"))
      (node (ref "U10") (pin "7") (pinfunction "WC#_7") (pintype "input"))
      (node (ref "U11") (pin "5") (pinfunction "GND_5") (pintype "input"))
      (node (ref "U12") (pin "2") (pinfunction "2_2") (pintype "input"))
      (node (ref "U13") (pin "2") (pinfunction "GND_2") (pintype "input"))
      (node (ref "U5") (pin "1") (pinfunction "GND_1") (pintype "input"))
      (node (ref "U6") (pin "1") (pinfunction "GND_1") (pintype "input"))
      (node (ref "U7") (pin "23") (pinfunction "VSS_1_23") (pintype "input"))
      (node (ref "U7") (pin "35") (pinfunction "VSS_2_35") (pintype "input"))
      (node (ref "U7") (pin "47") (pinfunction "VSS_3_47") (pintype "input"))
      (node (ref "U7") (pin "8") (pinfunction "VSSA_8") (pintype "input"))
      (node (ref "U9") (pin "8") (pinfunction "E_8") (pintype "input"))
    )
    (net (code "12") (name "K11") (class "Default")
      (node (ref "CN1") (pin "1") (pinfunction "1_1") (pintype "input"))
      (node (ref "K1") (pin "3") (pinfunction "3_3") (pintype "input"))
    )
    (net (code "13") (name "K12") (class "Default")
      (node (ref "CN1") (pin "2") (pinfunction "2_2") (pintype "input"))
      (node (ref "K1") (pin "4") (pinfunction "4_4") (pintype "input"))
    )
    (net (code "14") (name "K21") (class "Default")
      (node (ref "CN2") (pin "1") (pinfunction "1_1") (pintype "input"))
      (node (ref "K2") (pin "3") (pinfunction "3_3") (pintype "input"))
    )
    (net (code "15") (name "K22") (class "Default")
      (node (ref "CN2") (pin "2") (pinfunction "2_2") (pintype "input"))
      (node (ref "K2") (pin "4") (pinfunction "4_4") (pintype "input"))
    )
    (net (code "16") (name "K31") (class "Default")
      (node (ref "CN3") (pin "1") (pinfunction "1_1") (pintype "input"))
      (node (ref "K3") (pin "3") (pinfunction "3_3") (pintype "input"))
    )
    (net (code "17") (name "K32") (class "Default")
      (node (ref "CN3") (pin "2") (pinfunction "2_2") (pintype "input"))
      (node (ref "K3") (pin "4") (pinfunction "4_4") (pintype "input"))
    )
    (net (code "18") (name "K41") (class "Default")
      (node (ref "CN4") (pin "1") (pinfunction "1_1") (pintype "input"))
      (node (ref "K4") (pin "3") (pinfunction "3_3") (pintype "input"))
    )
    (net (code "19") (name "K42") (class "Default")
      (node (ref "CN4") (pin "2") (pinfunction "2_2") (pintype "input"))
      (node (ref "K4") (pin "4") (pinfunction "4_4") (pintype "input"))
    )
    (net (code "20") (name "LINK#") (class "Default")
      (node (ref "J2") (pin "10") (pinfunction "10_10") (pintype "input"))
      (node (ref "J2") (pin "11") (pinfunction "11_11") (pintype "input"))
      (node (ref "U1") (pin "52") (pinfunction "LINK#_52") (pintype "input"))
    )
    (net (code "21") (name "M_C") (class "Default")
      (node (ref "R13") (pin "2") (pinfunction "2_2") (pintype "input"))
      (node (ref "U7") (pin "34") (pinfunction "PA13_34") (pintype "input"))
    )
    (net (code "22") (name "M_D") (class "Default")
      (node (ref "R12") (pin "2") (pinfunction "2_2") (pintype "input"))
      (node (ref "U7") (pin "37") (pinfunction "PA14_37") (pintype "input"))
    )
    (net (code "23") (name "M_DIR") (class "Default")
      (node (ref "R16") (pin "1") (pinfunction "1_1") (pintype "input"))
      (node (ref "U11") (pin "2") (pinfunction "#RE_2") (pintype "input"))
      (node (ref "U11") (pin "3") (pinfunction "DE_3") (pintype "input"))
      (node (ref "U7") (pin "33") (pinfunction "PA12_33") (pintype "input"))
    )
    (net (code "24") (name "M_IO_PA4") (class "Default")
      (node (ref "H2") (pin "1") (pinfunction "1_1") (pintype "input"))
      (node (ref "U7") (pin "14") (pinfunction "PA4_14") (pintype "input"))
    )
    (net (code "25") (name "M_IO_PA5") (class "Default")
      (node (ref "H2") (pin "3") (pinfunction "3_3") (pintype "input"))
      (node (ref "U7") (pin "15") (pinfunction "PA5_15") (pintype "input"))
    )
    (net (code "26") (name "M_IO_PA6") (class "Default")
      (node (ref "H2") (pin "5") (pinfunction "5_5") (pintype "input"))
      (node (ref "U7") (pin "16") (pinfunction "PA6_16") (pintype "input"))
    )
    (net (code "27") (name "M_IO_PA7") (class "Default")
      (node (ref "H2") (pin "7") (pinfunction "7_7") (pintype "input"))
      (node (ref "U7") (pin "17") (pinfunction "PA7_17") (pintype "input"))
    )
    (net (code "28") (name "M_IO_PB1") (class "Default")
      (node (ref "H2") (pin "2") (pinfunction "2_2") (pintype "input"))
      (node (ref "U7") (pin "19") (pinfunction "PB1_19") (pintype "input"))
    )
    (net (code "29") (name "M_IO_PB2") (class "Default")
      (node (ref "H2") (pin "4") (pinfunction "4_4") (pintype "input"))
      (node (ref "U7") (pin "20") (pinfunction "PB2_20") (pintype "input"))
    )
    (net (code "30") (name "M_IO_PB10") (class "Default")
      (node (ref "H2") (pin "6") (pinfunction "6_6") (pintype "input"))
      (node (ref "U7") (pin "21") (pinfunction "PB10_21") (pintype "input"))
    )
    (net (code "31") (name "M_IO_PB11") (class "Default")
      (node (ref "H2") (pin "8") (pinfunction "8_8") (pintype "input"))
      (node (ref "U7") (pin "22") (pinfunction "PB11_22") (pintype "input"))
    )
    (net (code "32") (name "M_K1") (class "Default")
      (node (ref "U7") (pin "10") (pinfunction "PA0-WKUP_10") (pintype "input"))
      (node (ref "U9") (pin "1") (pinfunction "1B_1") (pintype "input"))
      (node (ref "U9") (pin "2") (pinfunction "2B_2") (pintype "input"))
    )
    (net (code "33") (name "M_K2") (class "Default")
      (node (ref "U7") (pin "11") (pinfunction "PA1_11") (pintype "input"))
      (node (ref "U9") (pin "3") (pinfunction "3B_3") (pintype "input"))
      (node (ref "U9") (pin "4") (pinfunction "4B_4") (pintype "input"))
    )
    (net (code "34") (name "M_K3") (class "Default")
      (node (ref "U7") (pin "12") (pinfunction "PA2_12") (pintype "input"))
      (node (ref "U9") (pin "5") (pinfunction "5B_5") (pintype "input"))
      (node (ref "U9") (pin "6") (pinfunction "6B_6") (pintype "input"))
    )
    (net (code "35") (name "M_K4") (class "Default")
      (node (ref "U7") (pin "13") (pinfunction "PA3_13") (pintype "input"))
      (node (ref "U9") (pin "7") (pinfunction "7B_7") (pintype "input"))
    )
    (net (code "36") (name "M_KC1") (class "Default")
      (node (ref "K1") (pin "2") (pinfunction "2_2") (pintype "input"))
      (node (ref "U9") (pin "15") (pinfunction "2C_15") (pintype "input"))
      (node (ref "U9") (pin "16") (pinfunction "1C_16") (pintype "input"))
    )
    (net (code "37") (name "M_KC2") (class "Default")
      (node (ref "K2") (pin "2") (pinfunction "2_2") (pintype "input"))
      (node (ref "U9") (pin "13") (pinfunction "4C_13") (pintype "input"))
      (node (ref "U9") (pin "14") (pinfunction "3C_14") (pintype "input"))
    )
    (net (code "38") (name "M_KC3") (class "Default")
      (node (ref "K3") (pin "2") (pinfunction "2_2") (pintype "input"))
      (node (ref "U9") (pin "11") (pinfunction "6C_11") (pintype "input"))
      (node (ref "U9") (pin "12") (pinfunction "5C_12") (pintype "input"))
    )
    (net (code "39") (name "M_KC4") (class "Default")
      (node (ref "K4") (pin "2") (pinfunction "2_2") (pintype "input"))
      (node (ref "U9") (pin "10") (pinfunction "7C_10") (pintype "input"))
    )
    (net (code "40") (name "M_RST#") (class "Default")
      (node (ref "C28") (pin "1") (pinfunction "1_1") (pintype "input"))
      (node (ref "R11") (pin "1") (pinfunction "1_1") (pintype "input"))
      (node (ref "U7") (pin "7") (pinfunction "NRST_7") (pintype "input"))
    )
    (net (code "41") (name "M_RXD") (class "Default")
      (node (ref "R18") (pin "2") (pinfunction "2_2") (pintype "input"))
      (node (ref "U11") (pin "1") (pinfunction "RO_1") (pintype "input"))
      (node (ref "U7") (pin "31") (pinfunction "PA10_31") (pintype "input"))
    )
    (net (code "42") (name "M_SCL") (class "Default")
      (node (ref "R15") (pin "2") (pinfunction "2_2") (pintype "input"))
      (node (ref "U10") (pin "6") (pinfunction "SCL_6") (pintype "input"))
      (node (ref "U7") (pin "42") (pinfunction "PB6_42") (pintype "input"))
    )
    (net (code "43") (name "M_SDA") (class "Default")
      (node (ref "R14") (pin "1") (pinfunction "1_1") (pintype "input"))
      (node (ref "U10") (pin "5") (pinfunction "SDA_5") (pintype "input"))
      (node (ref "U7") (pin "43") (pinfunction "PB7_43") (pintype "input"))
    )
    (net (code "44") (name "M_TXD") (class "Default")
      (node (ref "R17") (pin "1") (pinfunction "1_1") (pintype "input"))
      (node (ref "U11") (pin "4") (pinfunction "DI_4") (pintype "input"))
      (node (ref "U7") (pin "30") (pinfunction "PA9_30") (pintype "input"))
    )
    (net (code "45") (name "M_X1") (class "Default")
      (node (ref "C33") (pin "2") (pinfunction "2_2") (pintype "input"))
      (node (ref "U7") (pin "5") (pinfunction "PD0-OSCIN_5") (pintype "input"))
      (node (ref "U8") (pin "2") (pinfunction "2_2") (pintype "input"))
    )
    (net (code "46") (name "M_X2") (class "Default")
      (node (ref "C34") (pin "2") (pinfunction "2_2") (pintype "input"))
      (node (ref "U7") (pin "6") (pinfunction "PD1-OSCOUT_6") (pintype "input"))
      (node (ref "U8") (pin "1") (pinfunction "1_1") (pintype "input"))
    )
    (net (code "47") (name "Net-(H1-Pad1)") (class "Default")
      (node (ref "H1") (pin "1") (pinfunction "1_1") (pintype "input"))
      (node (ref "R12") (pin "1") (pinfunction "1_1") (pintype "input"))
    )
    (net (code "48") (name "Net-(H1-Pad4)") (class "Default")
      (node (ref "H1") (pin "4") (pinfunction "4_4") (pintype "input"))
      (node (ref "R13") (pin "1") (pinfunction "1_1") (pintype "input"))
    )
    (net (code "49") (name "Net-(J2-CHS_GND)") (class "Default")
      (node (ref "J2") (pin "8") (pinfunction "CHS_GND_8") (pintype "input"))
      (node (ref "R2") (pin "1") (pinfunction "1_1") (pintype "input"))
    )
    (net (code "50") (name "Net-(J2-Pad9)") (class "Default")
      (node (ref "J2") (pin "9") (pinfunction "9_9") (pintype "input"))
      (node (ref "R6") (pin "1") (pinfunction "1_1") (pintype "input"))
    )
    (net (code "51") (name "Net-(J2-Pad12)") (class "Default")
      (node (ref "J2") (pin "12") (pinfunction "12_12") (pintype "input"))
      (node (ref "R7") (pin "1") (pinfunction "1_1") (pintype "input"))
    )
    (net (code "52") (name "Net-(U1-RSETE)") (class "Default")
      (node (ref "R4") (pin "1") (pinfunction "1_1") (pintype "input"))
      (node (ref "U1") (pin "1") (pinfunction "RSETE_1") (pintype "input"))
    )
    (net (code "53") (name "Net-(U1-TXD)") (class "Default")
      (node (ref "R1") (pin "1") (pinfunction "1_1") (pintype "input"))
      (node (ref "U1") (pin "58") (pinfunction "TXD_58") (pintype "input"))
    )
    (net (code "54") (name "Net-(U11-A)") (class "Default")
      (node (ref "CN5") (pin "1") (pinfunction "1_1") (pintype "input"))
      (node (ref "R19") (pin "1") (pinfunction "1_1") (pintype "input"))
      (node (ref "R21") (pin "2") (pinfunction "2_2") (pintype "input"))
      (node (ref "U11") (pin "6") (pinfunction "A_6") (pintype "input"))
    )
    (net (code "55") (name "Net-(U11-B)") (class "Default")
      (node (ref "CN5") (pin "2") (pinfunction "2_2") (pintype "input"))
      (node (ref "R20") (pin "2") (pinfunction "2_2") (pintype "input"))
      (node (ref "R21") (pin "1") (pinfunction "1_1") (pintype "input"))
      (node (ref "U11") (pin "7") (pinfunction "B_7") (pintype "input"))
    )
    (net (code "56") (name "PGND") (class "Default")
      (node (ref "J2") (pin "SH1") (pinfunction "SH1_SH1") (pintype "input"))
      (node (ref "J2") (pin "SH2") (pinfunction "SH2_SH2") (pintype "input"))
      (node (ref "TP1") (pin "1") (pinfunction "1_1") (pintype "input"))
    )
    (net (code "57") (name "RXN") (class "Default")
      (node (ref "J2") (pin "6") (pinfunction "RD-_6") (pintype "input"))
      (node (ref "R3") (pin "1") (pinfunction "1_1") (pintype "input"))
      (node (ref "U1") (pin "5") (pinfunction "RXN_5") (pintype "input"))
    )
    (net (code "58") (name "RXP") (class "Default")
      (node (ref "J2") (pin "3") (pinfunction "RD+_3") (pintype "input"))
      (node (ref "R5") (pin "1") (pinfunction "1_1") (pintype "input"))
      (node (ref "U1") (pin "4") (pinfunction "RXP_4") (pintype "input"))
    )
    (net (code "59") (name "SEN_OUT") (class "Default")
      (node (ref "C39") (pin "1") (pinfunction "1_1") (pintype "input"))
      (node (ref "R22") (pin "1") (pinfunction "1_1") (pintype "input"))
      (node (ref "U12") (pin "4") (pinfunction "4_4") (pintype "input"))
      (node (ref "U7") (pin "18") (pinfunction "PB0_18") (pintype "input"))
    )
    (net (code "60") (name "S_CTRL") (class "Default")
      (node (ref "R23") (pin "2") (pinfunction "2_2") (pintype "input"))
      (node (ref "U13") (pin "4") (pinfunction "EN#_4") (pintype "input"))
      (node (ref "U7") (pin "38") (pinfunction "PA15_38") (pintype "input"))
    )
    (net (code "61") (name "TXN") (class "Default")
      (node (ref "J2") (pin "2") (pinfunction "TD-_2") (pintype "input"))
      (node (ref "R8") (pin "1") (pinfunction "1_1") (pintype "input"))
      (node (ref "U1") (pin "8") (pinfunction "TXN_8") (pintype "input"))
    )
    (net (code "62") (name "TXP") (class "Default")
      (node (ref "J2") (pin "1") (pinfunction "TD+_1") (pintype "input"))
      (node (ref "R9") (pin "1") (pinfunction "1_1") (pintype "input"))
      (node (ref "U1") (pin "7") (pinfunction "TXP_7") (pintype "input"))
    )
    (net (code "63") (name "V_HU") (class "Default")
      (node (ref "C40") (pin "2") (pinfunction "2_2") (pintype "input"))
      (node (ref "C42") (pin "2") (pinfunction "2_2") (pintype "input"))
      (node (ref "U12") (pin "1") (pinfunction "1_1") (pintype "input"))
      (node (ref "U13") (pin "1") (pinfunction "VOUT_1") (pintype "input"))
    )
    (net (code "64") (name "XI") (class "Default")
      (node (ref "C16") (pin "2") (pinfunction "2_2") (pintype "input"))
      (node (ref "U1") (pin "10") (pinfunction "XI_10") (pintype "input"))
      (node (ref "X1") (pin "2") (pinfunction "OSC2_2") (pintype "input"))
    )
    (net (code "65") (name "XO") (class "Default")
      (node (ref "C17") (pin "2") (pinfunction "2_2") (pintype "input"))
      (node (ref "U1") (pin "11") (pinfunction "XO_11") (pintype "input"))
      (node (ref "X1") (pin "1") (pinfunction "OSC1_1") (pintype "input"))
    )
    (net (code "66") (name "unconnected-(J2-NC-Pad7)") (class "Default")
      (node (ref "J2") (pin "7") (pinfunction "NC_7") (pintype "input+no_connect"))
    )
    (net (code "67") (name "unconnected-(OLED1-GND-Pad1)") (class "Default")
      (node (ref "OLED1") (pin "1") (pinfunction "GND_1") (pintype "input"))
    )
    (net (code "68") (name "unconnected-(OLED1-SCL-Pad3)") (class "Default")
      (node (ref "OLED1") (pin "3") (pinfunction "SCL_3") (pintype "input"))
    )
    (net (code "69") (name "unconnected-(OLED1-SDA-Pad4)") (class "Default")
      (node (ref "OLED1") (pin "4") (pinfunction "SDA_4") (pintype "input"))
    )
    (net (code "70") (name "unconnected-(OLED1-VCC-Pad2)") (class "Default")
      (node (ref "OLED1") (pin "2") (pinfunction "VCC_2") (pintype "input"))
    )
    (net (code "71") (name "unconnected-(U1-GPIO0-Pad22)") (class "Default")
      (node (ref "U1") (pin "22") (pinfunction "GPIO0_22") (pintype "input+no_connect"))
    )
    (net (code "72") (name "unconnected-(U1-GPIO1-Pad23)") (class "Default")
      (node (ref "U1") (pin "23") (pinfunction "GPIO1_23") (pintype "input+no_connect"))
    )
    (net (code "73") (name "unconnected-(U1-GPIO2-Pad24)") (class "Default")
      (node (ref "U1") (pin "24") (pinfunction "GPIO2_24") (pintype "input+no_connect"))
    )
    (net (code "74") (name "unconnected-(U1-GPIO4-Pad32)") (class "Default")
      (node (ref "U1") (pin "32") (pinfunction "GPIO4_32") (pintype "input+no_connect"))
    )
    (net (code "75") (name "unconnected-(U1-GPIO5-Pad33)") (class "Default")
      (node (ref "U1") (pin "33") (pinfunction "GPIO5_33") (pintype "input+no_connect"))
    )
    (net (code "76") (name "unconnected-(U1-GPIO6-Pad34)") (class "Default")
      (node (ref "U1") (pin "34") (pinfunction "GPIO6_34") (pintype "input+no_connect"))
    )
    (net (code "77") (name "unconnected-(U1-GPIO7-Pad35)") (class "Default")
      (node (ref "U1") (pin "35") (pinfunction "GPIO7_35") (pintype "input+no_connect"))
    )
    (net (code "78") (name "unconnected-(U1-NC-Pad14)") (class "Default")
      (node (ref "U1") (pin "14") (pinfunction "NC_14") (pintype "input+no_connect"))
    )
    (net (code "79") (name "unconnected-(U1-NC-Pad15)") (class "Default")
      (node (ref "U1") (pin "15") (pinfunction "NC_15") (pintype "input+no_connect"))
    )
    (net (code "80") (name "unconnected-(U1-NC-Pad16)") (class "Default")
      (node (ref "U1") (pin "16") (pinfunction "NC_16") (pintype "input+no_connect"))
    )
    (net (code "81") (name "unconnected-(U1-NC-Pad30)") (class "Default")
      (node (ref "U1") (pin "30") (pinfunction "NC_30") (pintype "input+no_connect"))
    )
    (net (code "82") (name "unconnected-(U1-NC-Pad31)") (class "Default")
      (node (ref "U1") (pin "31") (pinfunction "NC_31") (pintype "input+no_connect"))
    )
    (net (code "83") (name "unconnected-(U1-NC-Pad38)") (class "Default")
      (node (ref "U1") (pin "38") (pinfunction "NC_38") (pintype "input+no_connect"))
    )
    (net (code "84") (name "unconnected-(U1-NC-Pad39)") (class "Default")
      (node (ref "U1") (pin "39") (pinfunction "NC_39") (pintype "input+no_connect"))
    )
    (net (code "85") (name "unconnected-(U1-NC-Pad46)") (class "Default")
      (node (ref "U1") (pin "46") (pinfunction "NC_46") (pintype "input+no_connect"))
    )
    (net (code "86") (name "unconnected-(U1-NC-Pad47)") (class "Default")
      (node (ref "U1") (pin "47") (pinfunction "NC_47") (pintype "input+no_connect"))
    )
    (net (code "87") (name "unconnected-(U1-NC-Pad50)") (class "Default")
      (node (ref "U1") (pin "50") (pinfunction "NC_50") (pintype "input+no_connect"))
    )
    (net (code "88") (name "unconnected-(U1-NC-Pad51)") (class "Default")
      (node (ref "U1") (pin "51") (pinfunction "NC_51") (pintype "input+no_connect"))
    )
    (net (code "89") (name "unconnected-(U1-NC-Pad53)") (class "Default")
      (node (ref "U1") (pin "53") (pinfunction "NC_53") (pintype "input+no_connect"))
    )
    (net (code "90") (name "unconnected-(U1-NC-Pad55)") (class "Default")
      (node (ref "U1") (pin "55") (pinfunction "NC_55") (pintype "input+no_connect"))
    )
    (net (code "91") (name "unconnected-(U1-NC-Pad56)") (class "Default")
      (node (ref "U1") (pin "56") (pinfunction "NC_56") (pintype "input+no_connect"))
    )
    (net (code "92") (name "unconnected-(U1-RDY#GPIO3-Pad25)") (class "Default")
      (node (ref "U1") (pin "25") (pinfunction "RDY#GPIO3_25") (pintype "input+no_connect"))
    )
    (net (code "93") (name "unconnected-(U1-RST-Pad26)") (class "Default")
      (node (ref "U1") (pin "26") (pinfunction "RST_26") (pintype "input+no_connect"))
    )
    (net (code "94") (name "unconnected-(U1-RXD-Pad57)") (class "Default")
      (node (ref "U1") (pin "57") (pinfunction "RXD_57") (pintype "input+no_connect"))
    )
    (net (code "95") (name "unconnected-(U1-SEL-Pad27)") (class "Default")
      (node (ref "U1") (pin "27") (pinfunction "SEL_27") (pintype "input+no_connect"))
    )
    (net (code "96") (name "unconnected-(U7-PB3-Pad39)") (class "Default")
      (node (ref "U7") (pin "39") (pinfunction "PB3_39") (pintype "input+no_connect"))
    )
    (net (code "97") (name "unconnected-(U7-PB4-Pad40)") (class "Default")
      (node (ref "U7") (pin "40") (pinfunction "PB4_40") (pintype "input+no_connect"))
    )
    (net (code "98") (name "unconnected-(U7-PB5-Pad41)") (class "Default")
      (node (ref "U7") (pin "41") (pinfunction "PB5_41") (pintype "input+no_connect"))
    )
    (net (code "99") (name "unconnected-(U7-PB8-Pad45)") (class "Default")
      (node (ref "U7") (pin "45") (pinfunction "PB8_45") (pintype "input+no_connect"))
    )
    (net (code "100") (name "unconnected-(U7-PB9-Pad46)") (class "Default")
      (node (ref "U7") (pin "46") (pinfunction "PB9_46") (pintype "input+no_connect"))
    )
    (net (code "101") (name "unconnected-(U7-PC13-TAMPER-RTC-Pad2)") (class "Default")
      (node (ref "U7") (pin "2") (pinfunction "PC13-TAMPER-RTC_2") (pintype "input+no_connect"))
    )
    (net (code "102") (name "unconnected-(U7-PC14-OSC32IN-Pad3)") (class "Default")
      (node (ref "U7") (pin "3") (pinfunction "PC14-OSC32IN_3") (pintype "input+no_connect"))
    )
    (net (code "103") (name "unconnected-(U7-PC15-OSC32OUT-Pad4)") (class "Default")
      (node (ref "U7") (pin "4") (pinfunction "PC15-OSC32OUT_4") (pintype "input+no_connect"))
    )
    (net (code "104") (name "unconnected-(U13-FAULT-Pad5)") (class "Default")
      (node (ref "U13") (pin "5") (pinfunction "FAULT_5") (pintype "input+no_connect"))
    )
  )
)
